# MINI_SAM_2017-01-002.net
KiCad netlist of a schematic drawn in EAGLE
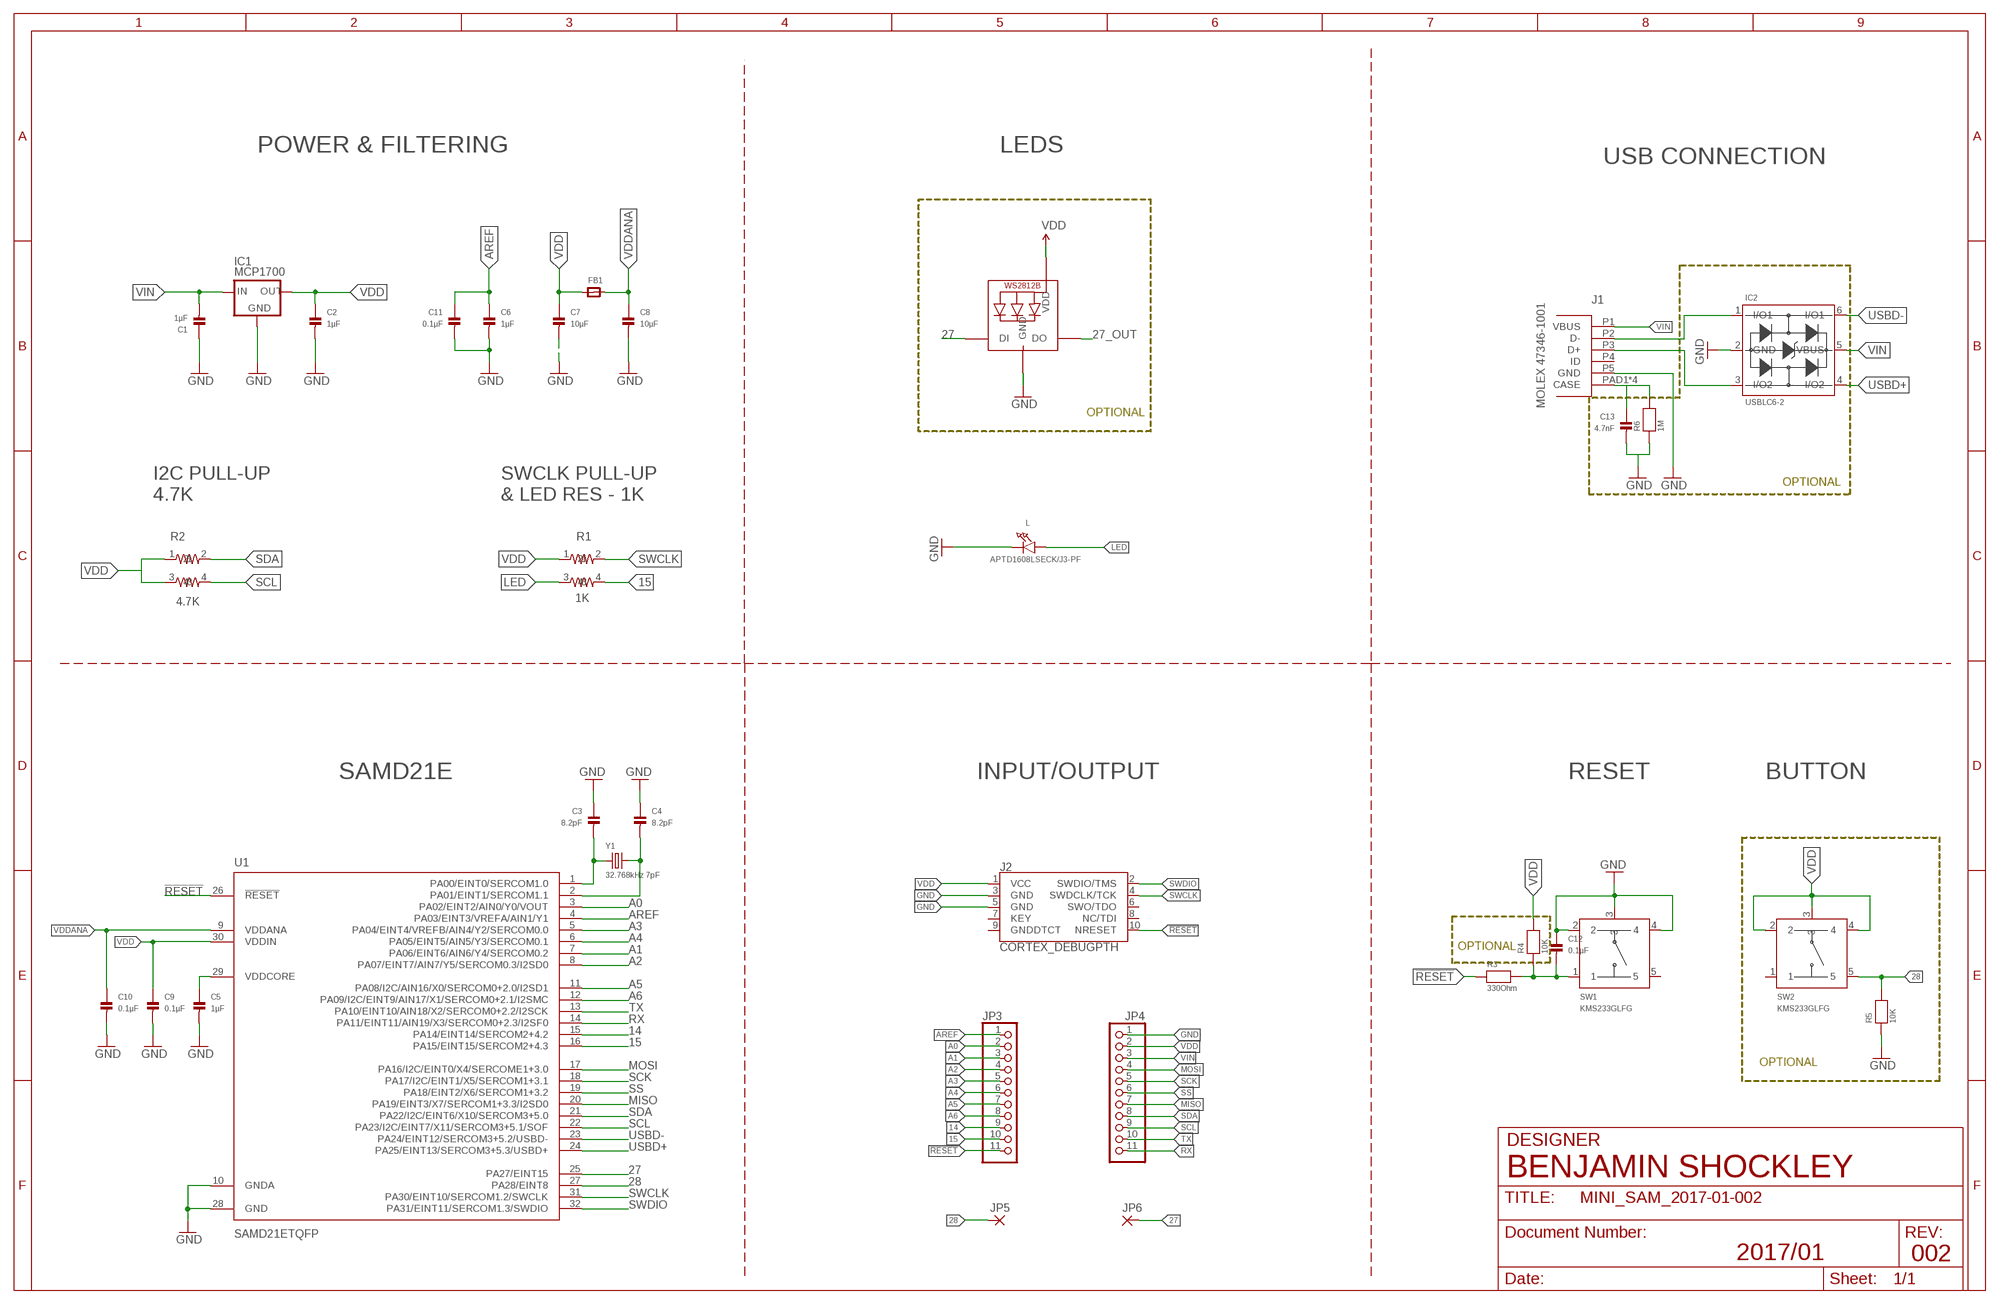
[diagram p0: schematic, sheet 1]

(export (version "E")
  (design (tool "Eeschema 10.0.6"))
  (components
    (comp (ref "C1")
      (value "1µF")
      (footprint "eagle-import:_0805MP")
      (libsource (lib "eagle-import") (part "CAP_CERAMIC_0805MP"))
    )
    (comp (ref "C2")
      (value "1µF")
      (footprint "eagle-import:_0805MP")
      (libsource (lib "eagle-import") (part "CAP_CERAMIC_0805MP"))
    )
    (comp (ref "C3")
      (value "8.2pF")
      (footprint "eagle-import:_0805MP")
      (libsource (lib "eagle-import") (part "CAP_CERAMIC_0805MP"))
    )
    (comp (ref "C4")
      (value "8.2pF")
      (footprint "eagle-import:_0805MP")
      (libsource (lib "eagle-import") (part "CAP_CERAMIC_0805MP"))
    )
    (comp (ref "C5")
      (value "1µF")
      (footprint "eagle-import:_0805MP")
      (libsource (lib "eagle-import") (part "CAP_CERAMIC_0805MP"))
    )
    (comp (ref "C6")
      (value "1µF")
      (footprint "eagle-import:_0805MP")
      (libsource (lib "eagle-import") (part "CAP_CERAMIC_0805MP"))
    )
    (comp (ref "C7")
      (value "10µF")
      (footprint "eagle-import:_0805MP")
      (libsource (lib "eagle-import") (part "CAP_CERAMIC_0805MP"))
    )
    (comp (ref "C8")
      (value "10µF")
      (footprint "eagle-import:_0805MP")
      (libsource (lib "eagle-import") (part "CAP_CERAMIC_0805MP"))
    )
    (comp (ref "C9")
      (value "0.1µF")
      (footprint "eagle-import:_0805MP")
      (libsource (lib "eagle-import") (part "CAP_CERAMIC_0805MP"))
    )
    (comp (ref "C10")
      (value "0.1µF")
      (footprint "eagle-import:_0805MP")
      (libsource (lib "eagle-import") (part "CAP_CERAMIC_0805MP"))
    )
    (comp (ref "C11")
      (value "0.1µF")
      (footprint "eagle-import:_0805MP")
      (libsource (lib "eagle-import") (part "CAP_CERAMIC_0805MP"))
    )
    (comp (ref "C12")
      (value "0.1µF")
      (footprint "eagle-import:_0805MP")
      (libsource (lib "eagle-import") (part "CAP_CERAMIC_0805MP"))
    )
    (comp (ref "C13")
      (value "4.7nF")
      (footprint "eagle-import:_0805MP")
      (libsource (lib "eagle-import") (part "CAP_CERAMIC_0805MP"))
    )
    (comp (ref "FB1")
      (value "FERRITE_0805MP")
      (footprint "eagle-import:_0805MP")
      (libsource (lib "eagle-import") (part "FERRITE_0805MP"))
    )
    (comp (ref "IC1")
      (value "MCP1700")
      (footprint "eagle-import:SOT23")
      (libsource (lib "eagle-import") (part "MCP1700"))
    )
    (comp (ref "IC2")
      (value "USBLC6-2")
      (footprint "eagle-import:SOT23-6L")
      (libsource (lib "eagle-import") (part "USBLC6-2"))
    )
    (comp (ref "J1")
      (value "MOLEX_47346-100147346")
      (footprint "eagle-import:MOLEX_47346-1001")
      (libsource (lib "eagle-import") (part "MOLEX_47346-100147346"))
    )
    (comp (ref "J2")
      (value "CORTEX_DEBUGPTH")
      (footprint "eagle-import:2X5-PTH-1.27MM")
      (libsource (lib "eagle-import") (part "CORTEX_DEBUGPTH"))
    )
    (comp (ref "JP3")
      (value "PINHD-1X111X11_SMT")
      (footprint "eagle-import:1X11_SMT")
      (libsource (lib "eagle-import") (part "PINHD-1X111X11_SMT"))
    )
    (comp (ref "JP4")
      (value "PINHD-1X111X11_SMT")
      (footprint "eagle-import:1X11_SMT")
      (libsource (lib "eagle-import") (part "PINHD-1X111X11_SMT"))
    )
    (comp (ref "JP5")
      (value "FR11_PAD2MMX1MM")
      (footprint "eagle-import:SMD2MMX1MM")
      (libsource (lib "eagle-import") (part "FR11_PAD2MMX1MM"))
    )
    (comp (ref "JP6")
      (value "FR11_PAD2MMX1MM")
      (footprint "eagle-import:SMD2MMX1MM")
      (libsource (lib "eagle-import") (part "FR11_PAD2MMX1MM"))
    )
    (comp (ref "L")
      (value "APTD1608LSECK/J3-PF")
      (footprint "eagle-import:CHIPLED_0603_NOOUTLINE")
      (libsource (lib "eagle-import") (part "LED0603_NOOUTLINE"))
    )
    (comp (ref "R1")
      (value "1K")
      (footprint "eagle-import:RESISTOR_ARRAY_0606")
      (libsource (lib "eagle-import") (part "RESISTOR_ARRAY_2"))
    )
    (comp (ref "R2")
      (value "4.7K")
      (footprint "eagle-import:RESISTOR_ARRAY_0606")
      (libsource (lib "eagle-import") (part "RESISTOR_ARRAY_2"))
    )
    (comp (ref "R3")
      (value "330Ohm")
      (footprint "eagle-import:_0805MP")
      (libsource (lib "eagle-import") (part "RESISTOR_0805MP"))
    )
    (comp (ref "R4")
      (value "10K")
      (footprint "eagle-import:_0805MP")
      (libsource (lib "eagle-import") (part "RESISTOR_0805MP"))
    )
    (comp (ref "R5")
      (value "10K")
      (footprint "eagle-import:_0805MP")
      (libsource (lib "eagle-import") (part "RESISTOR_0805MP"))
    )
    (comp (ref "R6")
      (value "1M")
      (footprint "eagle-import:_0805MP")
      (libsource (lib "eagle-import") (part "RESISTOR_0805MP"))
    )
    (comp (ref "STATUS")
      (value "WS2812B3535")
      (footprint "eagle-import:LED3535")
      (libsource (lib "eagle-import") (part "WS2812B3535"))
    )
    (comp (ref "SW1")
      (value "KMS233GLFG")
      (footprint "eagle-import:KMS_SWITCH")
      (libsource (lib "eagle-import") (part "KMS_SWITCHKMS"))
    )
    (comp (ref "SW2")
      (value "KMS233GLFG")
      (footprint "eagle-import:KMS_SWITCH")
      (libsource (lib "eagle-import") (part "KMS_SWITCHKMS"))
    )
    (comp (ref "U1")
      (value "SAMD21ETQFP")
      (footprint "eagle-import:TQFP32-08")
      (libsource (lib "eagle-import") (part "SAMD21ETQFP"))
    )
    (comp (ref "Y1")
      (value "32.768kHz 7pF")
      (footprint "eagle-import:_0805MP")
      (libsource (lib "eagle-import") (part "CRYSTAL0805PACKAGE"))
    )
  )
  (nets
    (net (code "1") (name "/27_OUT") (class "Default")
      (node (ref "STATUS") (pin "3") (pinfunction "DO_3") (pintype "output"))
    )
    (net (code "2") (name "/~{RESET}") (class "Default")
      (node (ref "J2") (pin "10") (pinfunction "NRESET_10") (pintype "bidirectional"))
      (node (ref "JP3") (pin "11") (pinfunction "11_11") (pintype "passive"))
      (node (ref "R3") (pin "1") (pinfunction "1_1") (pintype "passive"))
      (node (ref "U1") (pin "26") (pinfunction "~{RESET}_26") (pintype "bidirectional"))
    )
    (net (code "3") (name "14") (class "Default")
      (node (ref "JP3") (pin "9") (pinfunction "9_9") (pintype "passive"))
      (node (ref "U1") (pin "15") (pinfunction "PA14/EINT14/SERCOM2+4.2_15") (pintype "bidirectional"))
    )
    (net (code "4") (name "15") (class "Default")
      (node (ref "JP3") (pin "10") (pinfunction "10_10") (pintype "passive"))
      (node (ref "R1") (pin "4") (pinfunction "4_4") (pintype "passive"))
      (node (ref "U1") (pin "16") (pinfunction "PA15/EINT15/SERCOM2+4.3_16") (pintype "bidirectional"))
    )
    (net (code "5") (name "27") (class "Default")
      (node (ref "JP6") (pin "P$1") (pinfunction "P_P$1") (pintype "passive"))
      (node (ref "STATUS") (pin "1") (pinfunction "DI_1") (pintype "input"))
      (node (ref "U1") (pin "25") (pinfunction "PA27/EINT15_25") (pintype "bidirectional"))
    )
    (net (code "6") (name "28") (class "Default")
      (node (ref "JP5") (pin "P$1") (pinfunction "P_P$1") (pintype "passive"))
      (node (ref "R5") (pin "2") (pinfunction "2_2") (pintype "passive"))
      (node (ref "SW2") (pin "5") (pinfunction "5_5") (pintype "bidirectional"))
      (node (ref "U1") (pin "27") (pinfunction "PA28/EINT8_27") (pintype "bidirectional"))
    )
    (net (code "7") (name "A0") (class "Default")
      (node (ref "JP3") (pin "2") (pinfunction "2_2") (pintype "passive"))
      (node (ref "U1") (pin "3") (pinfunction "PA02/EINT2/AIN0/Y0/VOUT_3") (pintype "bidirectional"))
    )
    (net (code "8") (name "A1") (class "Default")
      (node (ref "JP3") (pin "3") (pinfunction "3_3") (pintype "passive"))
      (node (ref "U1") (pin "7") (pinfunction "PA06/EINT6/AIN6/Y4/SERCOM0.2_7") (pintype "bidirectional"))
    )
    (net (code "9") (name "A2") (class "Default")
      (node (ref "JP3") (pin "4") (pinfunction "4_4") (pintype "passive"))
      (node (ref "U1") (pin "8") (pinfunction "PA07/EINT7/AIN7/Y5/SERCOM0.3/I2SD0_8") (pintype "bidirectional"))
    )
    (net (code "10") (name "A3") (class "Default")
      (node (ref "JP3") (pin "5") (pinfunction "5_5") (pintype "passive"))
      (node (ref "U1") (pin "5") (pinfunction "PA04/EINT4/VREFB/AIN4/Y2/SERCOM0.0_5") (pintype "bidirectional"))
    )
    (net (code "11") (name "A4") (class "Default")
      (node (ref "JP3") (pin "6") (pinfunction "6_6") (pintype "passive"))
      (node (ref "U1") (pin "6") (pinfunction "PA05/EINT5/AIN5/Y3/SERCOM0.1_6") (pintype "bidirectional"))
    )
    (net (code "12") (name "A5") (class "Default")
      (node (ref "JP3") (pin "7") (pinfunction "7_7") (pintype "passive"))
      (node (ref "U1") (pin "11") (pinfunction "PA08/I2C/AIN16/X0/SERCOM0+2.0/I2SD1_11") (pintype "bidirectional"))
    )
    (net (code "13") (name "A6") (class "Default")
      (node (ref "JP3") (pin "8") (pinfunction "8_8") (pintype "passive"))
      (node (ref "U1") (pin "12") (pinfunction "PA09/I2C/EINT9/AIN17/X1/SERCOM0+2.1/I2SMC_12") (pintype "bidirectional"))
    )
    (net (code "14") (name "AREF") (class "Default")
      (node (ref "C11") (pin "1") (pinfunction "P$1_1") (pintype "passive"))
      (node (ref "C6") (pin "1") (pinfunction "P$1_1") (pintype "passive"))
      (node (ref "JP3") (pin "1") (pinfunction "1_1") (pintype "passive"))
      (node (ref "U1") (pin "4") (pinfunction "PA03/EINT3/VREFA/AIN1/Y1_4") (pintype "bidirectional"))
    )
    (net (code "15") (name "GND") (class "Default")
      (node (ref "C1") (pin "1") (pinfunction "P$1_1") (pintype "passive"))
      (node (ref "C10") (pin "2") (pinfunction "P$2_2") (pintype "passive"))
      (node (ref "C11") (pin "2") (pinfunction "P$2_2") (pintype "passive"))
      (node (ref "C12") (pin "1") (pinfunction "P$1_1") (pintype "passive"))
      (node (ref "C13") (pin "2") (pinfunction "P$2_2") (pintype "passive"))
      (node (ref "C2") (pin "2") (pinfunction "P$2_2") (pintype "passive"))
      (node (ref "C3") (pin "1") (pinfunction "P$1_1") (pintype "passive"))
      (node (ref "C4") (pin "1") (pinfunction "P$1_1") (pintype "passive"))
      (node (ref "C5") (pin "2") (pinfunction "P$2_2") (pintype "passive"))
      (node (ref "C6") (pin "2") (pinfunction "P$2_2") (pintype "passive"))
      (node (ref "C7") (pin "2") (pinfunction "P$2_2") (pintype "passive"))
      (node (ref "C8") (pin "2") (pinfunction "P$2_2") (pintype "passive"))
      (node (ref "C9") (pin "2") (pinfunction "P$2_2") (pintype "passive"))
      (node (ref "IC1") (pin "1") (pinfunction "GND_1") (pintype "input"))
      (node (ref "IC2") (pin "2") (pinfunction "GND_2") (pintype "bidirectional"))
      (node (ref "J1") (pin "P5") (pinfunction "GND_P5") (pintype "power_in"))
      (node (ref "J2") (pin "3") (pinfunction "GND_3") (pintype "bidirectional"))
      (node (ref "J2") (pin "5") (pinfunction "GND_5") (pintype "bidirectional"))
      (node (ref "JP4") (pin "1") (pinfunction "1_1") (pintype "passive"))
      (node (ref "L") (pin "C") (pinfunction "C_C") (pintype "passive"))
      (node (ref "R5") (pin "1") (pinfunction "1_1") (pintype "passive"))
      (node (ref "R6") (pin "1") (pinfunction "1_1") (pintype "passive"))
      (node (ref "STATUS") (pin "4") (pinfunction "GND_4") (pintype "power_in"))
      (node (ref "SW1") (pin "2") (pinfunction "2_2") (pintype "bidirectional"))
      (node (ref "SW1") (pin "3") (pinfunction "3_3") (pintype "bidirectional"))
      (node (ref "SW1") (pin "4") (pinfunction "4_4") (pintype "bidirectional"))
      (node (ref "U1") (pin "10") (pinfunction "GNDA_10") (pintype "power_in"))
      (node (ref "U1") (pin "28") (pinfunction "GND_28") (pintype "power_in"))
    )
    (net (code "16") (name "LED") (class "Default")
      (node (ref "L") (pin "A") (pinfunction "A_A") (pintype "passive"))
      (node (ref "R1") (pin "3") (pinfunction "3_3") (pintype "passive"))
    )
    (net (code "17") (name "MISO") (class "Default")
      (node (ref "JP4") (pin "7") (pinfunction "7_7") (pintype "passive"))
      (node (ref "U1") (pin "20") (pinfunction "PA19/EINT3/X7/SERCOM1+3.3/I2SD0_20") (pintype "bidirectional"))
    )
    (net (code "18") (name "MOSI") (class "Default")
      (node (ref "JP4") (pin "4") (pinfunction "4_4") (pintype "passive"))
      (node (ref "U1") (pin "17") (pinfunction "PA16/I2C/EINT0/X4/SERCOME1+3.0_17") (pintype "bidirectional"))
    )
    (net (code "19") (name "Net-(C3-P$2)") (class "Default")
      (node (ref "C3") (pin "2") (pinfunction "P$2_2") (pintype "passive"))
      (node (ref "U1") (pin "1") (pinfunction "PA00/EINT0/SERCOM1.0_1") (pintype "bidirectional"))
      (node (ref "Y1") (pin "1") (pinfunction "1_1") (pintype "passive"))
    )
    (net (code "20") (name "Net-(C4-P$2)") (class "Default")
      (node (ref "C4") (pin "2") (pinfunction "P$2_2") (pintype "passive"))
      (node (ref "U1") (pin "2") (pinfunction "PA01/EINT1/SERCOM1.1_2") (pintype "bidirectional"))
      (node (ref "Y1") (pin "2") (pinfunction "2_2") (pintype "passive"))
    )
    (net (code "21") (name "Net-(C5-P$1)") (class "Default")
      (node (ref "C5") (pin "1") (pinfunction "P$1_1") (pintype "passive"))
      (node (ref "U1") (pin "29") (pinfunction "VDDCORE_29") (pintype "power_in"))
    )
    (net (code "22") (name "Net-(C12-P$2)") (class "Default")
      (node (ref "C12") (pin "2") (pinfunction "P$2_2") (pintype "passive"))
      (node (ref "R3") (pin "2") (pinfunction "2_2") (pintype "passive"))
      (node (ref "R4") (pin "1") (pinfunction "1_1") (pintype "passive"))
      (node (ref "SW1") (pin "1") (pinfunction "1_1") (pintype "bidirectional"))
    )
    (net (code "23") (name "Net-(C13-P$1)") (class "Default")
      (node (ref "C13") (pin "1") (pinfunction "P$1_1") (pintype "passive"))
      (node (ref "J1") (pin "PAD1") (pinfunction "CASE_PAD1") (pintype "bidirectional"))
      (node (ref "J1") (pin "PAD2") (pinfunction "CASE_PAD2") (pintype "bidirectional"))
      (node (ref "J1") (pin "PAD3") (pinfunction "CASE_PAD3") (pintype "bidirectional"))
      (node (ref "J1") (pin "PAD4") (pinfunction "CASE_PAD4") (pintype "bidirectional"))
      (node (ref "R6") (pin "2") (pinfunction "2_2") (pintype "passive"))
    )
    (net (code "24") (name "Net-(J1-D+)") (class "Default")
      (node (ref "IC2") (pin "3") (pinfunction "I/O2_3") (pintype "bidirectional"))
      (node (ref "J1") (pin "P3") (pinfunction "D+_P3") (pintype "bidirectional"))
    )
    (net (code "25") (name "Net-(J1-D-)") (class "Default")
      (node (ref "IC2") (pin "1") (pinfunction "I/O1_1") (pintype "bidirectional"))
      (node (ref "J1") (pin "P2") (pinfunction "D-_P2") (pintype "bidirectional"))
    )
    (net (code "26") (name "RX") (class "Default")
      (node (ref "JP4") (pin "11") (pinfunction "11_11") (pintype "passive"))
      (node (ref "U1") (pin "14") (pinfunction "PA11/EINT11/AIN19/X3/SERCOM0+2.3/I2SF0_14") (pintype "bidirectional"))
    )
    (net (code "27") (name "SCK") (class "Default")
      (node (ref "JP4") (pin "5") (pinfunction "5_5") (pintype "passive"))
      (node (ref "U1") (pin "18") (pinfunction "PA17/I2C/EINT1/X5/SERCOM1+3.1_18") (pintype "bidirectional"))
    )
    (net (code "28") (name "SCL") (class "Default")
      (node (ref "JP4") (pin "9") (pinfunction "9_9") (pintype "passive"))
      (node (ref "R2") (pin "4") (pinfunction "4_4") (pintype "passive"))
      (node (ref "U1") (pin "22") (pinfunction "PA23/I2C/EINT7/X11/SERCOM3+5.1/SOF_22") (pintype "bidirectional"))
    )
    (net (code "29") (name "SDA") (class "Default")
      (node (ref "JP4") (pin "8") (pinfunction "8_8") (pintype "passive"))
      (node (ref "R2") (pin "2") (pinfunction "2_2") (pintype "passive"))
      (node (ref "U1") (pin "21") (pinfunction "PA22/I2C/EINT6/X10/SERCOM3+5.0_21") (pintype "bidirectional"))
    )
    (net (code "30") (name "SS") (class "Default")
      (node (ref "JP4") (pin "6") (pinfunction "6_6") (pintype "passive"))
      (node (ref "U1") (pin "19") (pinfunction "PA18/EINT2/X6/SERCOM1+3.2_19") (pintype "bidirectional"))
    )
    (net (code "31") (name "SWCLK") (class "Default")
      (node (ref "J2") (pin "4") (pinfunction "SWDCLK/TCK_4") (pintype "bidirectional"))
      (node (ref "R1") (pin "2") (pinfunction "2_2") (pintype "passive"))
      (node (ref "U1") (pin "31") (pinfunction "PA30/EINT10/SERCOM1.2/SWCLK_31") (pintype "bidirectional"))
    )
    (net (code "32") (name "SWDIO") (class "Default")
      (node (ref "J2") (pin "2") (pinfunction "SWDIO/TMS_2") (pintype "bidirectional"))
      (node (ref "U1") (pin "32") (pinfunction "PA31/EINT11/SERCOM1.3/SWDIO_32") (pintype "bidirectional"))
    )
    (net (code "33") (name "TX") (class "Default")
      (node (ref "JP4") (pin "10") (pinfunction "10_10") (pintype "passive"))
      (node (ref "U1") (pin "13") (pinfunction "PA10/EINT10/AIN18/X2/SERCOM0+2.2/I2SCK_13") (pintype "bidirectional"))
    )
    (net (code "34") (name "USBD+") (class "Default")
      (node (ref "IC2") (pin "4") (pinfunction "I/O2_4") (pintype "bidirectional"))
      (node (ref "U1") (pin "24") (pinfunction "PA25/EINT13/SERCOM3+5.3/USBD+_24") (pintype "bidirectional"))
    )
    (net (code "35") (name "USBD-") (class "Default")
      (node (ref "IC2") (pin "6") (pinfunction "I/O1_6") (pintype "bidirectional"))
      (node (ref "U1") (pin "23") (pinfunction "PA24/EINT12/SERCOM3+5.2/USBD-_23") (pintype "bidirectional"))
    )
    (net (code "36") (name "VDD") (class "Default")
      (node (ref "C2") (pin "1") (pinfunction "P$1_1") (pintype "passive"))
      (node (ref "C7") (pin "1") (pinfunction "P$1_1") (pintype "passive"))
      (node (ref "C9") (pin "1") (pinfunction "P$1_1") (pintype "passive"))
      (node (ref "FB1") (pin "1") (pinfunction "P$1_1") (pintype "passive"))
      (node (ref "IC1") (pin "2") (pinfunction "OUT_2") (pintype "passive"))
      (node (ref "J2") (pin "1") (pinfunction "VCC_1") (pintype "bidirectional"))
      (node (ref "JP4") (pin "2") (pinfunction "2_2") (pintype "passive"))
      (node (ref "R1") (pin "1") (pinfunction "1_1") (pintype "passive"))
      (node (ref "R2") (pin "1") (pinfunction "1_1") (pintype "passive"))
      (node (ref "R2") (pin "3") (pinfunction "3_3") (pintype "passive"))
      (node (ref "R4") (pin "2") (pinfunction "2_2") (pintype "passive"))
      (node (ref "STATUS") (pin "2") (pinfunction "VDD_2") (pintype "power_in"))
      (node (ref "SW2") (pin "2") (pinfunction "2_2") (pintype "bidirectional"))
      (node (ref "SW2") (pin "3") (pinfunction "3_3") (pintype "bidirectional"))
      (node (ref "SW2") (pin "4") (pinfunction "4_4") (pintype "bidirectional"))
      (node (ref "U1") (pin "30") (pinfunction "VDDIN_30") (pintype "power_in"))
    )
    (net (code "37") (name "VDDANA") (class "Default")
      (node (ref "C10") (pin "1") (pinfunction "P$1_1") (pintype "passive"))
      (node (ref "C8") (pin "1") (pinfunction "P$1_1") (pintype "passive"))
      (node (ref "FB1") (pin "2") (pinfunction "P$2_2") (pintype "passive"))
      (node (ref "U1") (pin "9") (pinfunction "VDDANA_9") (pintype "power_in"))
    )
    (net (code "38") (name "VIN") (class "Default")
      (node (ref "C1") (pin "2") (pinfunction "P$2_2") (pintype "passive"))
      (node (ref "IC1") (pin "3") (pinfunction "IN_3") (pintype "input"))
      (node (ref "IC2") (pin "5") (pinfunction "VBUS_5") (pintype "bidirectional"))
      (node (ref "J1") (pin "P1") (pinfunction "VBUS_P1") (pintype "power_in"))
      (node (ref "JP4") (pin "3") (pinfunction "3_3") (pintype "passive"))
    )
    (net (code "39") (name "unconnected-(J1-ID-PadP4)") (class "Default")
      (node (ref "J1") (pin "P4") (pinfunction "ID_P4") (pintype "bidirectional"))
    )
    (net (code "40") (name "unconnected-(J2-GNDDTCT-Pad9)") (class "Default")
      (node (ref "J2") (pin "9") (pinfunction "GNDDTCT_9") (pintype "bidirectional"))
    )
    (net (code "41") (name "unconnected-(J2-KEY-Pad7)") (class "Default")
      (node (ref "J2") (pin "7") (pinfunction "KEY_7") (pintype "bidirectional"))
    )
    (net (code "42") (name "unconnected-(J2-NC{slash}TDI-Pad8)") (class "Default")
      (node (ref "J2") (pin "8") (pinfunction "NC/TDI_8") (pintype "bidirectional"))
    )
    (net (code "43") (name "unconnected-(J2-SWO{slash}TDO-Pad6)") (class "Default")
      (node (ref "J2") (pin "6") (pinfunction "SWO/TDO_6") (pintype "bidirectional"))
    )
    (net (code "44") (name "unconnected-(SW1-Pad5)") (class "Default")
      (node (ref "SW1") (pin "5") (pinfunction "5_5") (pintype "bidirectional"))
    )
    (net (code "45") (name "unconnected-(SW2-Pad1)") (class "Default")
      (node (ref "SW2") (pin "1") (pinfunction "1_1") (pintype "bidirectional"))
    )
  )
)
